# IC_Adapter_2x20_Panel.net
KiCad netlist of a schematic drawn in EAGLE
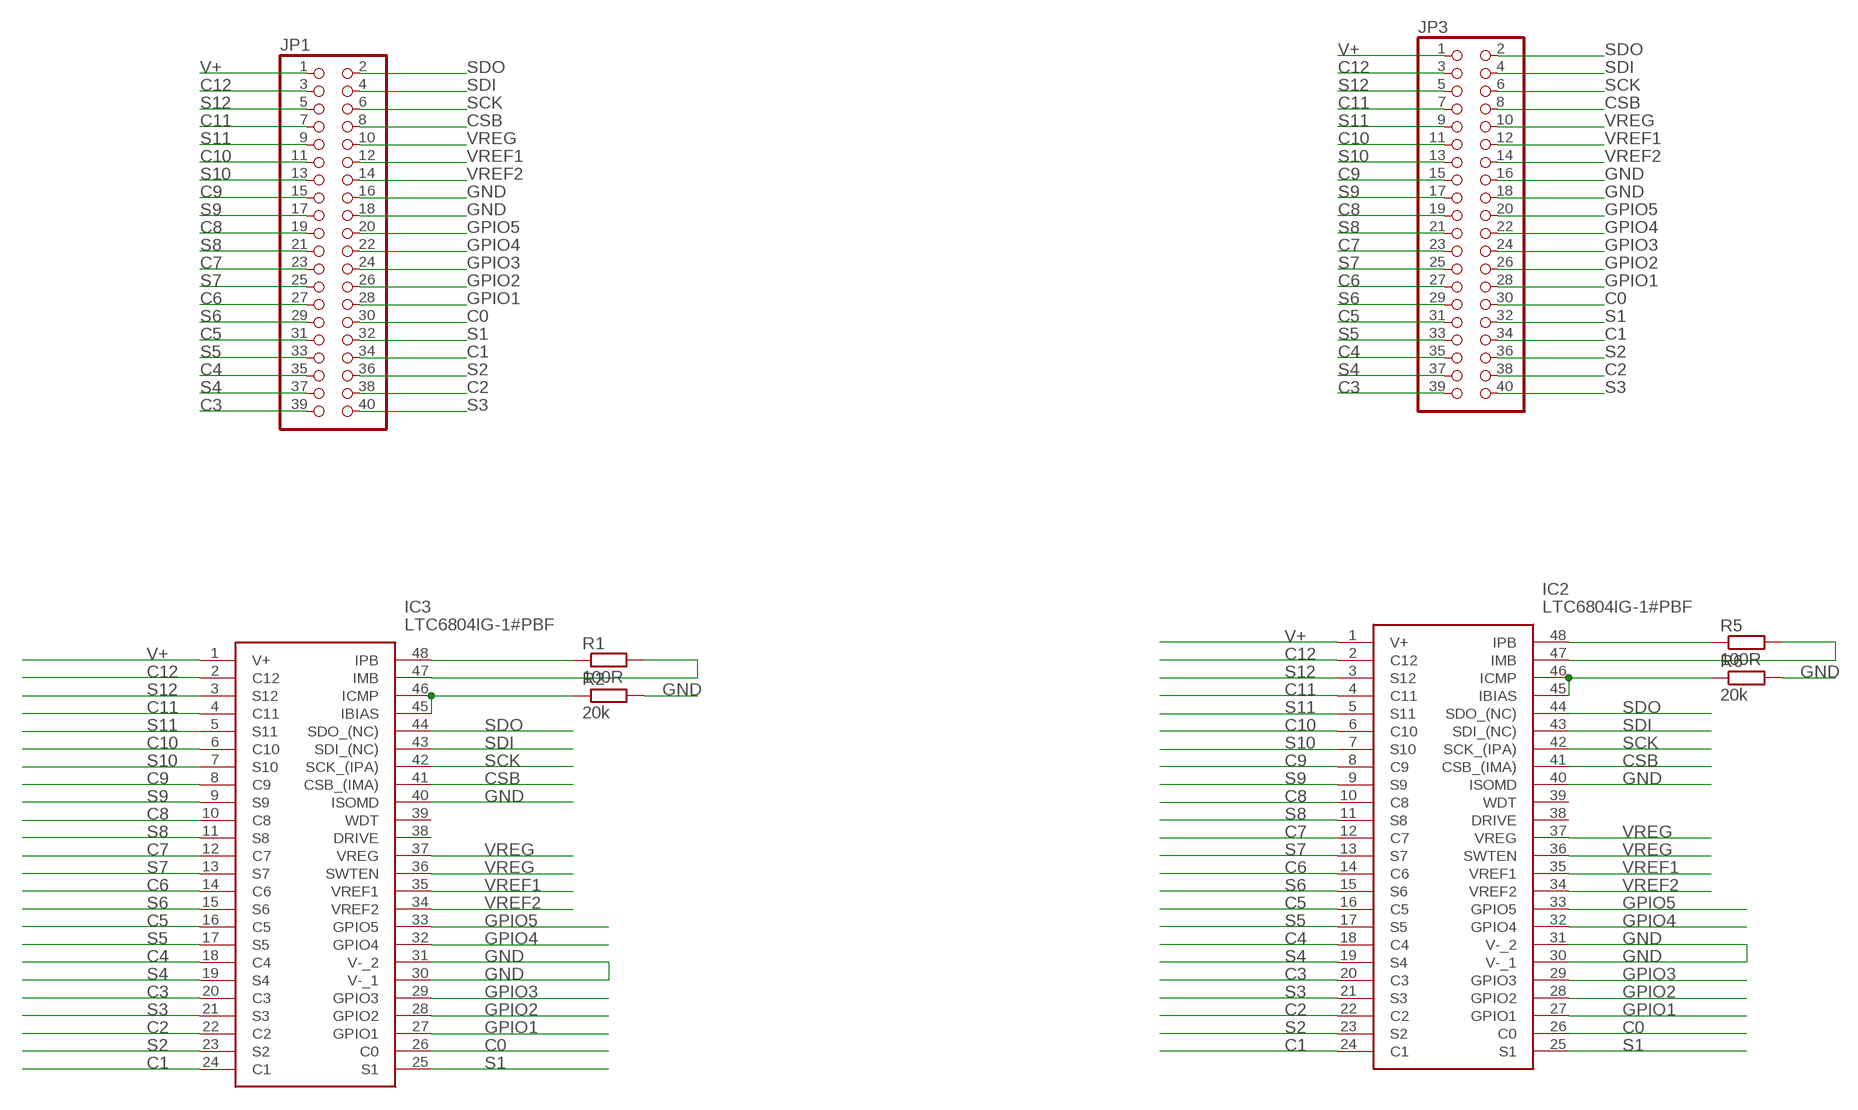
[diagram p0: schematic, sheet 1, part 1 of 2]
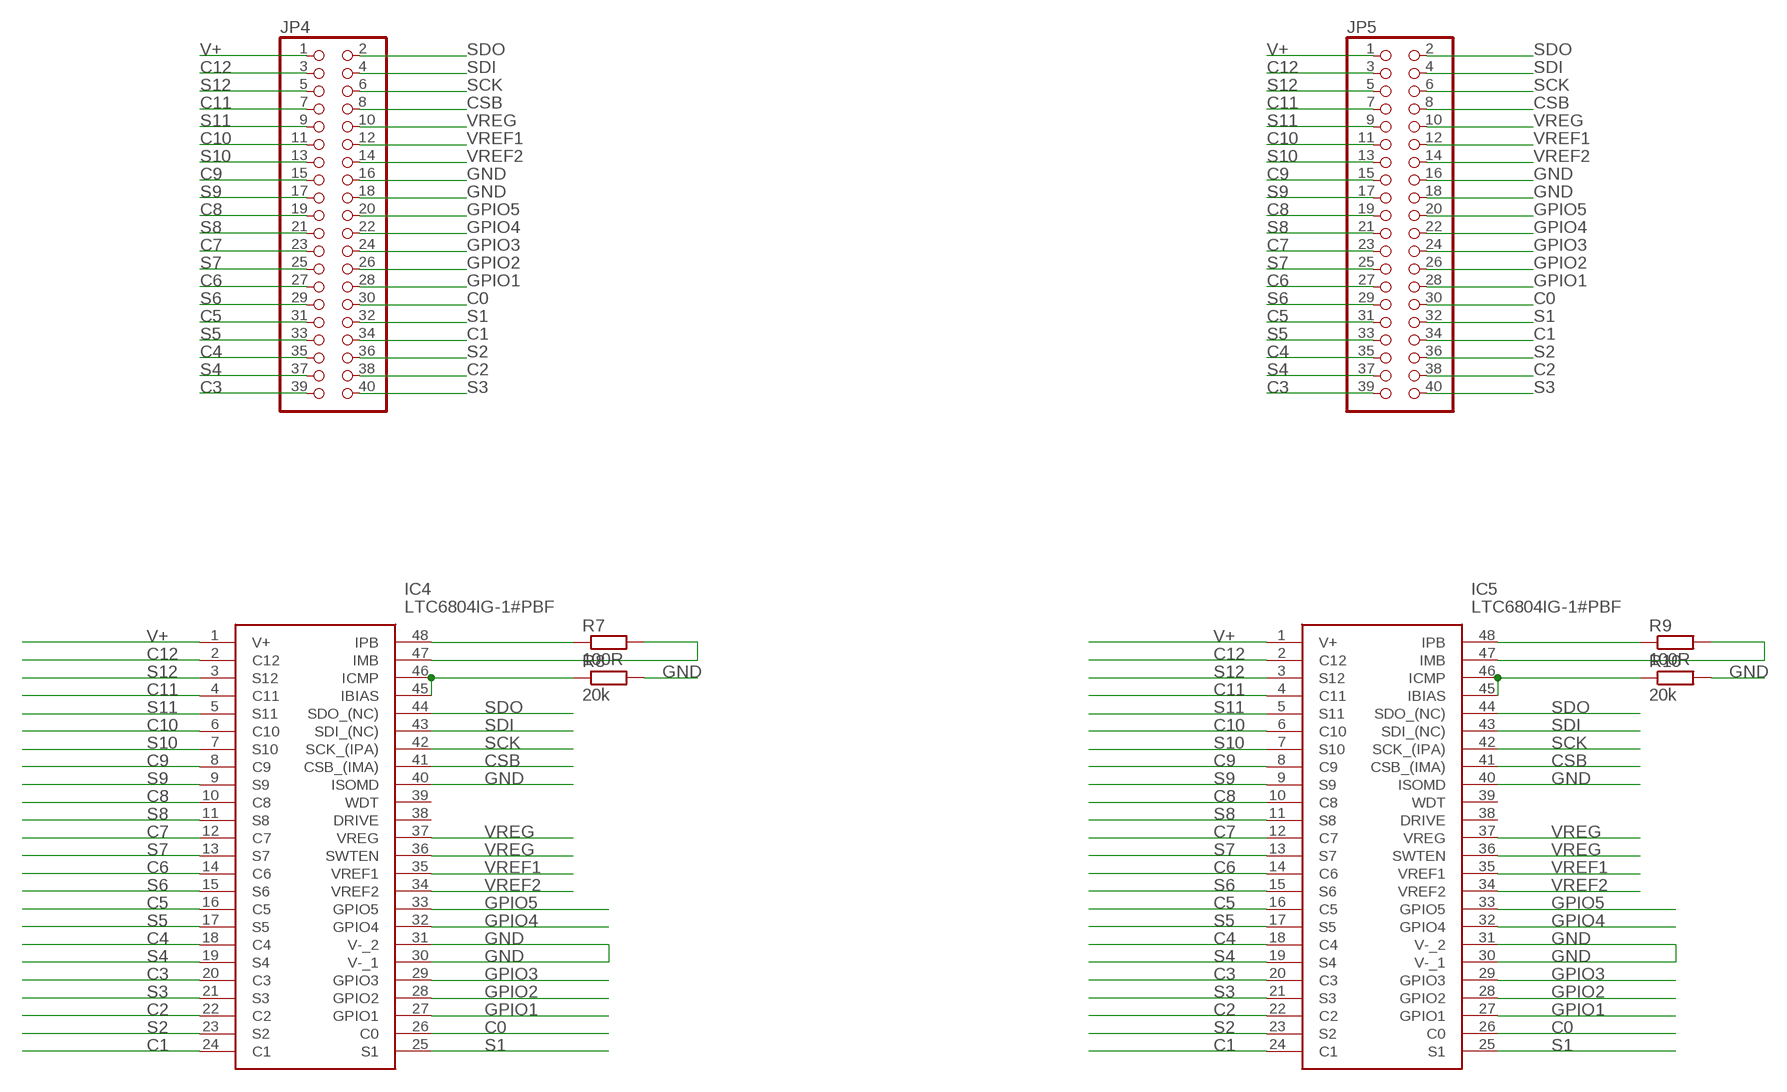
[diagram p1: schematic, sheet 1, part 2 of 2]

(export (version "E")
  (design (tool "Eeschema 10.0.6"))
  (components
    (comp (ref "IC2")
      (value "LTC6804IG-1#PBF")
      (footprint "eagle-import:SOP50P780X200-48N")
      (fields (field (name "MOUSER_PART_NUMBER") "584-LTC6804IG-1#PBF"))
      (libsource (lib "eagle-import") (part "LTC6804IG-1#PBF"))
    )
    (comp (ref "IC3")
      (value "LTC6804IG-1#PBF")
      (footprint "eagle-import:SOP50P780X200-48N")
      (fields (field (name "MOUSER_PART_NUMBER") "584-LTC6804IG-1#PBF"))
      (libsource (lib "eagle-import") (part "LTC6804IG-1#PBF"))
    )
    (comp (ref "IC4")
      (value "LTC6804IG-1#PBF")
      (footprint "eagle-import:SOP50P780X200-48N")
      (fields (field (name "MOUSER_PART_NUMBER") "584-LTC6804IG-1#PBF"))
      (libsource (lib "eagle-import") (part "LTC6804IG-1#PBF"))
    )
    (comp (ref "IC5")
      (value "LTC6804IG-1#PBF")
      (footprint "eagle-import:SOP50P780X200-48N")
      (fields (field (name "MOUSER_PART_NUMBER") "584-LTC6804IG-1#PBF"))
      (libsource (lib "eagle-import") (part "LTC6804IG-1#PBF"))
    )
    (comp (ref "JP1")
      (value "PINHD-2X20")
      (footprint "eagle-import:2X20")
      (libsource (lib "eagle-import") (part "PINHD-2X20"))
    )
    (comp (ref "JP3")
      (value "PINHD-2X20")
      (footprint "eagle-import:2X20")
      (libsource (lib "eagle-import") (part "PINHD-2X20"))
    )
    (comp (ref "JP4")
      (value "PINHD-2X20")
      (footprint "eagle-import:2X20")
      (libsource (lib "eagle-import") (part "PINHD-2X20"))
    )
    (comp (ref "JP5")
      (value "PINHD-2X20")
      (footprint "eagle-import:2X20")
      (libsource (lib "eagle-import") (part "PINHD-2X20"))
    )
    (comp (ref "R1")
      (value "100R")
      (footprint "eagle-import:R0805")
      (libsource (lib "eagle-import") (part "R-EU_R0805"))
    )
    (comp (ref "R2")
      (value "20k")
      (footprint "eagle-import:R0805")
      (libsource (lib "eagle-import") (part "R-EU_R0805"))
    )
    (comp (ref "R5")
      (value "100R")
      (footprint "eagle-import:R0805")
      (libsource (lib "eagle-import") (part "R-EU_R0805"))
    )
    (comp (ref "R6")
      (value "20k")
      (footprint "eagle-import:R0805")
      (libsource (lib "eagle-import") (part "R-EU_R0805"))
    )
    (comp (ref "R7")
      (value "100R")
      (footprint "eagle-import:R0805")
      (libsource (lib "eagle-import") (part "R-EU_R0805"))
    )
    (comp (ref "R8")
      (value "20k")
      (footprint "eagle-import:R0805")
      (libsource (lib "eagle-import") (part "R-EU_R0805"))
    )
    (comp (ref "R9")
      (value "100R")
      (footprint "eagle-import:R0805")
      (libsource (lib "eagle-import") (part "R-EU_R0805"))
    )
    (comp (ref "R10")
      (value "20k")
      (footprint "eagle-import:R0805")
      (libsource (lib "eagle-import") (part "R-EU_R0805"))
    )
  )
  (nets
    (net (code "1") (name "/C0") (class "Default")
      (node (ref "IC2") (pin "26") (pinfunction "C0_26") (pintype "bidirectional"))
      (node (ref "IC3") (pin "26") (pinfunction "C0_26") (pintype "bidirectional"))
      (node (ref "IC4") (pin "26") (pinfunction "C0_26") (pintype "bidirectional"))
      (node (ref "IC5") (pin "26") (pinfunction "C0_26") (pintype "bidirectional"))
      (node (ref "JP1") (pin "30") (pinfunction "30_30") (pintype "passive"))
      (node (ref "JP3") (pin "30") (pinfunction "30_30") (pintype "passive"))
      (node (ref "JP4") (pin "30") (pinfunction "30_30") (pintype "passive"))
      (node (ref "JP5") (pin "30") (pinfunction "30_30") (pintype "passive"))
    )
    (net (code "2") (name "/C1") (class "Default")
      (node (ref "IC2") (pin "24") (pinfunction "C1_24") (pintype "bidirectional"))
      (node (ref "IC3") (pin "24") (pinfunction "C1_24") (pintype "bidirectional"))
      (node (ref "IC4") (pin "24") (pinfunction "C1_24") (pintype "bidirectional"))
      (node (ref "IC5") (pin "24") (pinfunction "C1_24") (pintype "bidirectional"))
      (node (ref "JP1") (pin "34") (pinfunction "34_34") (pintype "passive"))
      (node (ref "JP3") (pin "34") (pinfunction "34_34") (pintype "passive"))
      (node (ref "JP4") (pin "34") (pinfunction "34_34") (pintype "passive"))
      (node (ref "JP5") (pin "34") (pinfunction "34_34") (pintype "passive"))
    )
    (net (code "3") (name "/C2") (class "Default")
      (node (ref "IC2") (pin "22") (pinfunction "C2_22") (pintype "bidirectional"))
      (node (ref "IC3") (pin "22") (pinfunction "C2_22") (pintype "bidirectional"))
      (node (ref "IC4") (pin "22") (pinfunction "C2_22") (pintype "bidirectional"))
      (node (ref "IC5") (pin "22") (pinfunction "C2_22") (pintype "bidirectional"))
      (node (ref "JP1") (pin "38") (pinfunction "38_38") (pintype "passive"))
      (node (ref "JP3") (pin "38") (pinfunction "38_38") (pintype "passive"))
      (node (ref "JP4") (pin "38") (pinfunction "38_38") (pintype "passive"))
      (node (ref "JP5") (pin "38") (pinfunction "38_38") (pintype "passive"))
    )
    (net (code "4") (name "/C3") (class "Default")
      (node (ref "IC2") (pin "20") (pinfunction "C3_20") (pintype "bidirectional"))
      (node (ref "IC3") (pin "20") (pinfunction "C3_20") (pintype "bidirectional"))
      (node (ref "IC4") (pin "20") (pinfunction "C3_20") (pintype "bidirectional"))
      (node (ref "IC5") (pin "20") (pinfunction "C3_20") (pintype "bidirectional"))
      (node (ref "JP1") (pin "39") (pinfunction "39_39") (pintype "passive"))
      (node (ref "JP3") (pin "39") (pinfunction "39_39") (pintype "passive"))
      (node (ref "JP4") (pin "39") (pinfunction "39_39") (pintype "passive"))
      (node (ref "JP5") (pin "39") (pinfunction "39_39") (pintype "passive"))
    )
    (net (code "5") (name "/C4") (class "Default")
      (node (ref "IC2") (pin "18") (pinfunction "C4_18") (pintype "bidirectional"))
      (node (ref "IC3") (pin "18") (pinfunction "C4_18") (pintype "bidirectional"))
      (node (ref "IC4") (pin "18") (pinfunction "C4_18") (pintype "bidirectional"))
      (node (ref "IC5") (pin "18") (pinfunction "C4_18") (pintype "bidirectional"))
      (node (ref "JP1") (pin "35") (pinfunction "35_35") (pintype "passive"))
      (node (ref "JP3") (pin "35") (pinfunction "35_35") (pintype "passive"))
      (node (ref "JP4") (pin "35") (pinfunction "35_35") (pintype "passive"))
      (node (ref "JP5") (pin "35") (pinfunction "35_35") (pintype "passive"))
    )
    (net (code "6") (name "/C5") (class "Default")
      (node (ref "IC2") (pin "16") (pinfunction "C5_16") (pintype "bidirectional"))
      (node (ref "IC3") (pin "16") (pinfunction "C5_16") (pintype "bidirectional"))
      (node (ref "IC4") (pin "16") (pinfunction "C5_16") (pintype "bidirectional"))
      (node (ref "IC5") (pin "16") (pinfunction "C5_16") (pintype "bidirectional"))
      (node (ref "JP1") (pin "31") (pinfunction "31_31") (pintype "passive"))
      (node (ref "JP3") (pin "31") (pinfunction "31_31") (pintype "passive"))
      (node (ref "JP4") (pin "31") (pinfunction "31_31") (pintype "passive"))
      (node (ref "JP5") (pin "31") (pinfunction "31_31") (pintype "passive"))
    )
    (net (code "7") (name "/C6") (class "Default")
      (node (ref "IC2") (pin "14") (pinfunction "C6_14") (pintype "bidirectional"))
      (node (ref "IC3") (pin "14") (pinfunction "C6_14") (pintype "bidirectional"))
      (node (ref "IC4") (pin "14") (pinfunction "C6_14") (pintype "bidirectional"))
      (node (ref "IC5") (pin "14") (pinfunction "C6_14") (pintype "bidirectional"))
      (node (ref "JP1") (pin "27") (pinfunction "27_27") (pintype "passive"))
      (node (ref "JP3") (pin "27") (pinfunction "27_27") (pintype "passive"))
      (node (ref "JP4") (pin "27") (pinfunction "27_27") (pintype "passive"))
      (node (ref "JP5") (pin "27") (pinfunction "27_27") (pintype "passive"))
    )
    (net (code "8") (name "/C7") (class "Default")
      (node (ref "IC2") (pin "12") (pinfunction "C7_12") (pintype "bidirectional"))
      (node (ref "IC3") (pin "12") (pinfunction "C7_12") (pintype "bidirectional"))
      (node (ref "IC4") (pin "12") (pinfunction "C7_12") (pintype "bidirectional"))
      (node (ref "IC5") (pin "12") (pinfunction "C7_12") (pintype "bidirectional"))
      (node (ref "JP1") (pin "23") (pinfunction "23_23") (pintype "passive"))
      (node (ref "JP3") (pin "23") (pinfunction "23_23") (pintype "passive"))
      (node (ref "JP4") (pin "23") (pinfunction "23_23") (pintype "passive"))
      (node (ref "JP5") (pin "23") (pinfunction "23_23") (pintype "passive"))
    )
    (net (code "9") (name "/C8") (class "Default")
      (node (ref "IC2") (pin "10") (pinfunction "C8_10") (pintype "bidirectional"))
      (node (ref "IC3") (pin "10") (pinfunction "C8_10") (pintype "bidirectional"))
      (node (ref "IC4") (pin "10") (pinfunction "C8_10") (pintype "bidirectional"))
      (node (ref "IC5") (pin "10") (pinfunction "C8_10") (pintype "bidirectional"))
      (node (ref "JP1") (pin "19") (pinfunction "19_19") (pintype "passive"))
      (node (ref "JP3") (pin "19") (pinfunction "19_19") (pintype "passive"))
      (node (ref "JP4") (pin "19") (pinfunction "19_19") (pintype "passive"))
      (node (ref "JP5") (pin "19") (pinfunction "19_19") (pintype "passive"))
    )
    (net (code "10") (name "/C9") (class "Default")
      (node (ref "IC2") (pin "8") (pinfunction "C9_8") (pintype "bidirectional"))
      (node (ref "IC3") (pin "8") (pinfunction "C9_8") (pintype "bidirectional"))
      (node (ref "IC4") (pin "8") (pinfunction "C9_8") (pintype "bidirectional"))
      (node (ref "IC5") (pin "8") (pinfunction "C9_8") (pintype "bidirectional"))
      (node (ref "JP1") (pin "15") (pinfunction "15_15") (pintype "passive"))
      (node (ref "JP3") (pin "15") (pinfunction "15_15") (pintype "passive"))
      (node (ref "JP4") (pin "15") (pinfunction "15_15") (pintype "passive"))
      (node (ref "JP5") (pin "15") (pinfunction "15_15") (pintype "passive"))
    )
    (net (code "11") (name "/C10") (class "Default")
      (node (ref "IC2") (pin "6") (pinfunction "C10_6") (pintype "bidirectional"))
      (node (ref "IC3") (pin "6") (pinfunction "C10_6") (pintype "bidirectional"))
      (node (ref "IC4") (pin "6") (pinfunction "C10_6") (pintype "bidirectional"))
      (node (ref "IC5") (pin "6") (pinfunction "C10_6") (pintype "bidirectional"))
      (node (ref "JP1") (pin "11") (pinfunction "11_11") (pintype "passive"))
      (node (ref "JP3") (pin "11") (pinfunction "11_11") (pintype "passive"))
      (node (ref "JP4") (pin "11") (pinfunction "11_11") (pintype "passive"))
      (node (ref "JP5") (pin "11") (pinfunction "11_11") (pintype "passive"))
    )
    (net (code "12") (name "/C11") (class "Default")
      (node (ref "IC2") (pin "4") (pinfunction "C11_4") (pintype "bidirectional"))
      (node (ref "IC3") (pin "4") (pinfunction "C11_4") (pintype "bidirectional"))
      (node (ref "IC4") (pin "4") (pinfunction "C11_4") (pintype "bidirectional"))
      (node (ref "IC5") (pin "4") (pinfunction "C11_4") (pintype "bidirectional"))
      (node (ref "JP1") (pin "7") (pinfunction "7_7") (pintype "passive"))
      (node (ref "JP3") (pin "7") (pinfunction "7_7") (pintype "passive"))
      (node (ref "JP4") (pin "7") (pinfunction "7_7") (pintype "passive"))
      (node (ref "JP5") (pin "7") (pinfunction "7_7") (pintype "passive"))
    )
    (net (code "13") (name "/C12") (class "Default")
      (node (ref "IC2") (pin "2") (pinfunction "C12_2") (pintype "bidirectional"))
      (node (ref "IC3") (pin "2") (pinfunction "C12_2") (pintype "bidirectional"))
      (node (ref "IC4") (pin "2") (pinfunction "C12_2") (pintype "bidirectional"))
      (node (ref "IC5") (pin "2") (pinfunction "C12_2") (pintype "bidirectional"))
      (node (ref "JP1") (pin "3") (pinfunction "3_3") (pintype "passive"))
      (node (ref "JP3") (pin "3") (pinfunction "3_3") (pintype "passive"))
      (node (ref "JP4") (pin "3") (pinfunction "3_3") (pintype "passive"))
      (node (ref "JP5") (pin "3") (pinfunction "3_3") (pintype "passive"))
    )
    (net (code "14") (name "/CSB") (class "Default")
      (node (ref "IC2") (pin "41") (pinfunction "CSB_(IMA)_41") (pintype "bidirectional"))
      (node (ref "IC3") (pin "41") (pinfunction "CSB_(IMA)_41") (pintype "bidirectional"))
      (node (ref "IC4") (pin "41") (pinfunction "CSB_(IMA)_41") (pintype "bidirectional"))
      (node (ref "IC5") (pin "41") (pinfunction "CSB_(IMA)_41") (pintype "bidirectional"))
      (node (ref "JP1") (pin "8") (pinfunction "8_8") (pintype "passive"))
      (node (ref "JP3") (pin "8") (pinfunction "8_8") (pintype "passive"))
      (node (ref "JP4") (pin "8") (pinfunction "8_8") (pintype "passive"))
      (node (ref "JP5") (pin "8") (pinfunction "8_8") (pintype "passive"))
    )
    (net (code "15") (name "/GND") (class "Default")
      (node (ref "IC2") (pin "30") (pinfunction "V-_1_30") (pintype "bidirectional"))
      (node (ref "IC2") (pin "31") (pinfunction "V-_2_31") (pintype "bidirectional"))
      (node (ref "IC2") (pin "40") (pinfunction "ISOMD_40") (pintype "bidirectional"))
      (node (ref "IC3") (pin "30") (pinfunction "V-_1_30") (pintype "bidirectional"))
      (node (ref "IC3") (pin "31") (pinfunction "V-_2_31") (pintype "bidirectional"))
      (node (ref "IC3") (pin "40") (pinfunction "ISOMD_40") (pintype "bidirectional"))
      (node (ref "IC4") (pin "30") (pinfunction "V-_1_30") (pintype "bidirectional"))
      (node (ref "IC4") (pin "31") (pinfunction "V-_2_31") (pintype "bidirectional"))
      (node (ref "IC4") (pin "40") (pinfunction "ISOMD_40") (pintype "bidirectional"))
      (node (ref "IC5") (pin "30") (pinfunction "V-_1_30") (pintype "bidirectional"))
      (node (ref "IC5") (pin "31") (pinfunction "V-_2_31") (pintype "bidirectional"))
      (node (ref "IC5") (pin "40") (pinfunction "ISOMD_40") (pintype "bidirectional"))
      (node (ref "JP1") (pin "16") (pinfunction "16_16") (pintype "passive"))
      (node (ref "JP1") (pin "18") (pinfunction "18_18") (pintype "passive"))
      (node (ref "JP3") (pin "16") (pinfunction "16_16") (pintype "passive"))
      (node (ref "JP3") (pin "18") (pinfunction "18_18") (pintype "passive"))
      (node (ref "JP4") (pin "16") (pinfunction "16_16") (pintype "passive"))
      (node (ref "JP4") (pin "18") (pinfunction "18_18") (pintype "passive"))
      (node (ref "JP5") (pin "16") (pinfunction "16_16") (pintype "passive"))
      (node (ref "JP5") (pin "18") (pinfunction "18_18") (pintype "passive"))
      (node (ref "R10") (pin "2") (pinfunction "2_2") (pintype "passive"))
      (node (ref "R2") (pin "2") (pinfunction "2_2") (pintype "passive"))
      (node (ref "R6") (pin "2") (pinfunction "2_2") (pintype "passive"))
      (node (ref "R8") (pin "2") (pinfunction "2_2") (pintype "passive"))
    )
    (net (code "16") (name "/GPIO1") (class "Default")
      (node (ref "IC2") (pin "27") (pinfunction "GPIO1_27") (pintype "bidirectional"))
      (node (ref "IC3") (pin "27") (pinfunction "GPIO1_27") (pintype "bidirectional"))
      (node (ref "IC4") (pin "27") (pinfunction "GPIO1_27") (pintype "bidirectional"))
      (node (ref "IC5") (pin "27") (pinfunction "GPIO1_27") (pintype "bidirectional"))
      (node (ref "JP1") (pin "28") (pinfunction "28_28") (pintype "passive"))
      (node (ref "JP3") (pin "28") (pinfunction "28_28") (pintype "passive"))
      (node (ref "JP4") (pin "28") (pinfunction "28_28") (pintype "passive"))
      (node (ref "JP5") (pin "28") (pinfunction "28_28") (pintype "passive"))
    )
    (net (code "17") (name "/GPIO2") (class "Default")
      (node (ref "IC2") (pin "28") (pinfunction "GPIO2_28") (pintype "bidirectional"))
      (node (ref "IC3") (pin "28") (pinfunction "GPIO2_28") (pintype "bidirectional"))
      (node (ref "IC4") (pin "28") (pinfunction "GPIO2_28") (pintype "bidirectional"))
      (node (ref "IC5") (pin "28") (pinfunction "GPIO2_28") (pintype "bidirectional"))
      (node (ref "JP1") (pin "26") (pinfunction "26_26") (pintype "passive"))
      (node (ref "JP3") (pin "26") (pinfunction "26_26") (pintype "passive"))
      (node (ref "JP4") (pin "26") (pinfunction "26_26") (pintype "passive"))
      (node (ref "JP5") (pin "26") (pinfunction "26_26") (pintype "passive"))
    )
    (net (code "18") (name "/GPIO3") (class "Default")
      (node (ref "IC2") (pin "29") (pinfunction "GPIO3_29") (pintype "bidirectional"))
      (node (ref "IC3") (pin "29") (pinfunction "GPIO3_29") (pintype "bidirectional"))
      (node (ref "IC4") (pin "29") (pinfunction "GPIO3_29") (pintype "bidirectional"))
      (node (ref "IC5") (pin "29") (pinfunction "GPIO3_29") (pintype "bidirectional"))
      (node (ref "JP1") (pin "24") (pinfunction "24_24") (pintype "passive"))
      (node (ref "JP3") (pin "24") (pinfunction "24_24") (pintype "passive"))
      (node (ref "JP4") (pin "24") (pinfunction "24_24") (pintype "passive"))
      (node (ref "JP5") (pin "24") (pinfunction "24_24") (pintype "passive"))
    )
    (net (code "19") (name "/GPIO4") (class "Default")
      (node (ref "IC2") (pin "32") (pinfunction "GPIO4_32") (pintype "bidirectional"))
      (node (ref "IC3") (pin "32") (pinfunction "GPIO4_32") (pintype "bidirectional"))
      (node (ref "IC4") (pin "32") (pinfunction "GPIO4_32") (pintype "bidirectional"))
      (node (ref "IC5") (pin "32") (pinfunction "GPIO4_32") (pintype "bidirectional"))
      (node (ref "JP1") (pin "22") (pinfunction "22_22") (pintype "passive"))
      (node (ref "JP3") (pin "22") (pinfunction "22_22") (pintype "passive"))
      (node (ref "JP4") (pin "22") (pinfunction "22_22") (pintype "passive"))
      (node (ref "JP5") (pin "22") (pinfunction "22_22") (pintype "passive"))
    )
    (net (code "20") (name "/GPIO5") (class "Default")
      (node (ref "IC2") (pin "33") (pinfunction "GPIO5_33") (pintype "bidirectional"))
      (node (ref "IC3") (pin "33") (pinfunction "GPIO5_33") (pintype "bidirectional"))
      (node (ref "IC4") (pin "33") (pinfunction "GPIO5_33") (pintype "bidirectional"))
      (node (ref "IC5") (pin "33") (pinfunction "GPIO5_33") (pintype "bidirectional"))
      (node (ref "JP1") (pin "20") (pinfunction "20_20") (pintype "passive"))
      (node (ref "JP3") (pin "20") (pinfunction "20_20") (pintype "passive"))
      (node (ref "JP4") (pin "20") (pinfunction "20_20") (pintype "passive"))
      (node (ref "JP5") (pin "20") (pinfunction "20_20") (pintype "passive"))
    )
    (net (code "21") (name "/S1") (class "Default")
      (node (ref "IC2") (pin "25") (pinfunction "S1_25") (pintype "bidirectional"))
      (node (ref "IC3") (pin "25") (pinfunction "S1_25") (pintype "bidirectional"))
      (node (ref "IC4") (pin "25") (pinfunction "S1_25") (pintype "bidirectional"))
      (node (ref "IC5") (pin "25") (pinfunction "S1_25") (pintype "bidirectional"))
      (node (ref "JP1") (pin "32") (pinfunction "32_32") (pintype "passive"))
      (node (ref "JP3") (pin "32") (pinfunction "32_32") (pintype "passive"))
      (node (ref "JP4") (pin "32") (pinfunction "32_32") (pintype "passive"))
      (node (ref "JP5") (pin "32") (pinfunction "32_32") (pintype "passive"))
    )
    (net (code "22") (name "/S2") (class "Default")
      (node (ref "IC2") (pin "23") (pinfunction "S2_23") (pintype "bidirectional"))
      (node (ref "IC3") (pin "23") (pinfunction "S2_23") (pintype "bidirectional"))
      (node (ref "IC4") (pin "23") (pinfunction "S2_23") (pintype "bidirectional"))
      (node (ref "IC5") (pin "23") (pinfunction "S2_23") (pintype "bidirectional"))
      (node (ref "JP1") (pin "36") (pinfunction "36_36") (pintype "passive"))
      (node (ref "JP3") (pin "36") (pinfunction "36_36") (pintype "passive"))
      (node (ref "JP4") (pin "36") (pinfunction "36_36") (pintype "passive"))
      (node (ref "JP5") (pin "36") (pinfunction "36_36") (pintype "passive"))
    )
    (net (code "23") (name "/S3") (class "Default")
      (node (ref "IC2") (pin "21") (pinfunction "S3_21") (pintype "bidirectional"))
      (node (ref "IC3") (pin "21") (pinfunction "S3_21") (pintype "bidirectional"))
      (node (ref "IC4") (pin "21") (pinfunction "S3_21") (pintype "bidirectional"))
      (node (ref "IC5") (pin "21") (pinfunction "S3_21") (pintype "bidirectional"))
      (node (ref "JP1") (pin "40") (pinfunction "40_40") (pintype "passive"))
      (node (ref "JP3") (pin "40") (pinfunction "40_40") (pintype "passive"))
      (node (ref "JP4") (pin "40") (pinfunction "40_40") (pintype "passive"))
      (node (ref "JP5") (pin "40") (pinfunction "40_40") (pintype "passive"))
    )
    (net (code "24") (name "/S4") (class "Default")
      (node (ref "IC2") (pin "19") (pinfunction "S4_19") (pintype "bidirectional"))
      (node (ref "IC3") (pin "19") (pinfunction "S4_19") (pintype "bidirectional"))
      (node (ref "IC4") (pin "19") (pinfunction "S4_19") (pintype "bidirectional"))
      (node (ref "IC5") (pin "19") (pinfunction "S4_19") (pintype "bidirectional"))
      (node (ref "JP1") (pin "37") (pinfunction "37_37") (pintype "passive"))
      (node (ref "JP3") (pin "37") (pinfunction "37_37") (pintype "passive"))
      (node (ref "JP4") (pin "37") (pinfunction "37_37") (pintype "passive"))
      (node (ref "JP5") (pin "37") (pinfunction "37_37") (pintype "passive"))
    )
    (net (code "25") (name "/S5") (class "Default")
      (node (ref "IC2") (pin "17") (pinfunction "S5_17") (pintype "bidirectional"))
      (node (ref "IC3") (pin "17") (pinfunction "S5_17") (pintype "bidirectional"))
      (node (ref "IC4") (pin "17") (pinfunction "S5_17") (pintype "bidirectional"))
      (node (ref "IC5") (pin "17") (pinfunction "S5_17") (pintype "bidirectional"))
      (node (ref "JP1") (pin "33") (pinfunction "33_33") (pintype "passive"))
      (node (ref "JP3") (pin "33") (pinfunction "33_33") (pintype "passive"))
      (node (ref "JP4") (pin "33") (pinfunction "33_33") (pintype "passive"))
      (node (ref "JP5") (pin "33") (pinfunction "33_33") (pintype "passive"))
    )
    (net (code "26") (name "/S6") (class "Default")
      (node (ref "IC2") (pin "15") (pinfunction "S6_15") (pintype "bidirectional"))
      (node (ref "IC3") (pin "15") (pinfunction "S6_15") (pintype "bidirectional"))
      (node (ref "IC4") (pin "15") (pinfunction "S6_15") (pintype "bidirectional"))
      (node (ref "IC5") (pin "15") (pinfunction "S6_15") (pintype "bidirectional"))
      (node (ref "JP1") (pin "29") (pinfunction "29_29") (pintype "passive"))
      (node (ref "JP3") (pin "29") (pinfunction "29_29") (pintype "passive"))
      (node (ref "JP4") (pin "29") (pinfunction "29_29") (pintype "passive"))
      (node (ref "JP5") (pin "29") (pinfunction "29_29") (pintype "passive"))
    )
    (net (code "27") (name "/S7") (class "Default")
      (node (ref "IC2") (pin "13") (pinfunction "S7_13") (pintype "bidirectional"))
      (node (ref "IC3") (pin "13") (pinfunction "S7_13") (pintype "bidirectional"))
      (node (ref "IC4") (pin "13") (pinfunction "S7_13") (pintype "bidirectional"))
      (node (ref "IC5") (pin "13") (pinfunction "S7_13") (pintype "bidirectional"))
      (node (ref "JP1") (pin "25") (pinfunction "25_25") (pintype "passive"))
      (node (ref "JP3") (pin "25") (pinfunction "25_25") (pintype "passive"))
      (node (ref "JP4") (pin "25") (pinfunction "25_25") (pintype "passive"))
      (node (ref "JP5") (pin "25") (pinfunction "25_25") (pintype "passive"))
    )
    (net (code "28") (name "/S8") (class "Default")
      (node (ref "IC2") (pin "11") (pinfunction "S8_11") (pintype "bidirectional"))
      (node (ref "IC3") (pin "11") (pinfunction "S8_11") (pintype "bidirectional"))
      (node (ref "IC4") (pin "11") (pinfunction "S8_11") (pintype "bidirectional"))
      (node (ref "IC5") (pin "11") (pinfunction "S8_11") (pintype "bidirectional"))
      (node (ref "JP1") (pin "21") (pinfunction "21_21") (pintype "passive"))
      (node (ref "JP3") (pin "21") (pinfunction "21_21") (pintype "passive"))
      (node (ref "JP4") (pin "21") (pinfunction "21_21") (pintype "passive"))
      (node (ref "JP5") (pin "21") (pinfunction "21_21") (pintype "passive"))
    )
    (net (code "29") (name "/S9") (class "Default")
      (node (ref "IC2") (pin "9") (pinfunction "S9_9") (pintype "bidirectional"))
      (node (ref "IC3") (pin "9") (pinfunction "S9_9") (pintype "bidirectional"))
      (node (ref "IC4") (pin "9") (pinfunction "S9_9") (pintype "bidirectional"))
      (node (ref "IC5") (pin "9") (pinfunction "S9_9") (pintype "bidirectional"))
      (node (ref "JP1") (pin "17") (pinfunction "17_17") (pintype "passive"))
      (node (ref "JP3") (pin "17") (pinfunction "17_17") (pintype "passive"))
      (node (ref "JP4") (pin "17") (pinfunction "17_17") (pintype "passive"))
      (node (ref "JP5") (pin "17") (pinfunction "17_17") (pintype "passive"))
    )
    (net (code "30") (name "/S10") (class "Default")
      (node (ref "IC2") (pin "7") (pinfunction "S10_7") (pintype "bidirectional"))
      (node (ref "IC3") (pin "7") (pinfunction "S10_7") (pintype "bidirectional"))
      (node (ref "IC4") (pin "7") (pinfunction "S10_7") (pintype "bidirectional"))
      (node (ref "IC5") (pin "7") (pinfunction "S10_7") (pintype "bidirectional"))
      (node (ref "JP1") (pin "13") (pinfunction "13_13") (pintype "passive"))
      (node (ref "JP3") (pin "13") (pinfunction "13_13") (pintype "passive"))
      (node (ref "JP4") (pin "13") (pinfunction "13_13") (pintype "passive"))
      (node (ref "JP5") (pin "13") (pinfunction "13_13") (pintype "passive"))
    )
    (net (code "31") (name "/S11") (class "Default")
      (node (ref "IC2") (pin "5") (pinfunction "S11_5") (pintype "bidirectional"))
      (node (ref "IC3") (pin "5") (pinfunction "S11_5") (pintype "bidirectional"))
      (node (ref "IC4") (pin "5") (pinfunction "S11_5") (pintype "bidirectional"))
      (node (ref "IC5") (pin "5") (pinfunction "S11_5") (pintype "bidirectional"))
      (node (ref "JP1") (pin "9") (pinfunction "9_9") (pintype "passive"))
      (node (ref "JP3") (pin "9") (pinfunction "9_9") (pintype "passive"))
      (node (ref "JP4") (pin "9") (pinfunction "9_9") (pintype "passive"))
      (node (ref "JP5") (pin "9") (pinfunction "9_9") (pintype "passive"))
    )
    (net (code "32") (name "/S12") (class "Default")
      (node (ref "IC2") (pin "3") (pinfunction "S12_3") (pintype "bidirectional"))
      (node (ref "IC3") (pin "3") (pinfunction "S12_3") (pintype "bidirectional"))
      (node (ref "IC4") (pin "3") (pinfunction "S12_3") (pintype "bidirectional"))
      (node (ref "IC5") (pin "3") (pinfunction "S12_3") (pintype "bidirectional"))
      (node (ref "JP1") (pin "5") (pinfunction "5_5") (pintype "passive"))
      (node (ref "JP3") (pin "5") (pinfunction "5_5") (pintype "passive"))
      (node (ref "JP4") (pin "5") (pinfunction "5_5") (pintype "passive"))
      (node (ref "JP5") (pin "5") (pinfunction "5_5") (pintype "passive"))
    )
    (net (code "33") (name "/SCK") (class "Default")
      (node (ref "IC2") (pin "42") (pinfunction "SCK_(IPA)_42") (pintype "bidirectional"))
      (node (ref "IC3") (pin "42") (pinfunction "SCK_(IPA)_42") (pintype "bidirectional"))
      (node (ref "IC4") (pin "42") (pinfunction "SCK_(IPA)_42") (pintype "bidirectional"))
      (node (ref "IC5") (pin "42") (pinfunction "SCK_(IPA)_42") (pintype "bidirectional"))
      (node (ref "JP1") (pin "6") (pinfunction "6_6") (pintype "passive"))
      (node (ref "JP3") (pin "6") (pinfunction "6_6") (pintype "passive"))
      (node (ref "JP4") (pin "6") (pinfunction "6_6") (pintype "passive"))
      (node (ref "JP5") (pin "6") (pinfunction "6_6") (pintype "passive"))
    )
    (net (code "34") (name "/SDI") (class "Default")
      (node (ref "IC2") (pin "43") (pinfunction "SDI_(NC)_43") (pintype "bidirectional"))
      (node (ref "IC3") (pin "43") (pinfunction "SDI_(NC)_43") (pintype "bidirectional"))
      (node (ref "IC4") (pin "43") (pinfunction "SDI_(NC)_43") (pintype "bidirectional"))
      (node (ref "IC5") (pin "43") (pinfunction "SDI_(NC)_43") (pintype "bidirectional"))
      (node (ref "JP1") (pin "4") (pinfunction "4_4") (pintype "passive"))
      (node (ref "JP3") (pin "4") (pinfunction "4_4") (pintype "passive"))
      (node (ref "JP4") (pin "4") (pinfunction "4_4") (pintype "passive"))
      (node (ref "JP5") (pin "4") (pinfunction "4_4") (pintype "passive"))
    )
    (net (code "35") (name "/SDO") (class "Default")
      (node (ref "IC2") (pin "44") (pinfunction "SDO_(NC)_44") (pintype "bidirectional"))
      (node (ref "IC3") (pin "44") (pinfunction "SDO_(NC)_44") (pintype "bidirectional"))
      (node (ref "IC4") (pin "44") (pinfunction "SDO_(NC)_44") (pintype "bidirectional"))
      (node (ref "IC5") (pin "44") (pinfunction "SDO_(NC)_44") (pintype "bidirectional"))
      (node (ref "JP1") (pin "2") (pinfunction "2_2") (pintype "passive"))
      (node (ref "JP3") (pin "2") (pinfunction "2_2") (pintype "passive"))
      (node (ref "JP4") (pin "2") (pinfunction "2_2") (pintype "passive"))
      (node (ref "JP5") (pin "2") (pinfunction "2_2") (pintype "passive"))
    )
    (net (code "36") (name "/V+") (class "Default")
      (node (ref "IC2") (pin "1") (pinfunction "V+_1") (pintype "bidirectional"))
      (node (ref "IC3") (pin "1") (pinfunction "V+_1") (pintype "bidirectional"))
      (node (ref "IC4") (pin "1") (pinfunction "V+_1") (pintype "bidirectional"))
      (node (ref "IC5") (pin "1") (pinfunction "V+_1") (pintype "bidirectional"))
      (node (ref "JP1") (pin "1") (pinfunction "1_1") (pintype "passive"))
      (node (ref "JP3") (pin "1") (pinfunction "1_1") (pintype "passive"))
      (node (ref "JP4") (pin "1") (pinfunction "1_1") (pintype "passive"))
      (node (ref "JP5") (pin "1") (pinfunction "1_1") (pintype "passive"))
    )
    (net (code "37") (name "/VREF1") (class "Default")
      (node (ref "IC2") (pin "35") (pinfunction "VREF1_35") (pintype "bidirectional"))
      (node (ref "IC3") (pin "35") (pinfunction "VREF1_35") (pintype "bidirectional"))
      (node (ref "IC4") (pin "35") (pinfunction "VREF1_35") (pintype "bidirectional"))
      (node (ref "IC5") (pin "35") (pinfunction "VREF1_35") (pintype "bidirectional"))
      (node (ref "JP1") (pin "12") (pinfunction "12_12") (pintype "passive"))
      (node (ref "JP3") (pin "12") (pinfunction "12_12") (pintype "passive"))
      (node (ref "JP4") (pin "12") (pinfunction "12_12") (pintype "passive"))
      (node (ref "JP5") (pin "12") (pinfunction "12_12") (pintype "passive"))
    )
    (net (code "38") (name "/VREF2") (class "Default")
      (node (ref "IC2") (pin "34") (pinfunction "VREF2_34") (pintype "bidirectional"))
      (node (ref "IC3") (pin "34") (pinfunction "VREF2_34") (pintype "bidirectional"))
      (node (ref "IC4") (pin "34") (pinfunction "VREF2_34") (pintype "bidirectional"))
      (node (ref "IC5") (pin "34") (pinfunction "VREF2_34") (pintype "bidirectional"))
      (node (ref "JP1") (pin "14") (pinfunction "14_14") (pintype "passive"))
      (node (ref "JP3") (pin "14") (pinfunction "14_14") (pintype "passive"))
      (node (ref "JP4") (pin "14") (pinfunction "14_14") (pintype "passive"))
      (node (ref "JP5") (pin "14") (pinfunction "14_14") (pintype "passive"))
    )
    (net (code "39") (name "/VREG") (class "Default")
      (node (ref "IC2") (pin "36") (pinfunction "SWTEN_36") (pintype "bidirectional"))
      (node (ref "IC2") (pin "37") (pinfunction "VREG_37") (pintype "bidirectional"))
      (node (ref "IC3") (pin "36") (pinfunction "SWTEN_36") (pintype "bidirectional"))
      (node (ref "IC3") (pin "37") (pinfunction "VREG_37") (pintype "bidirectional"))
      (node (ref "IC4") (pin "36") (pinfunction "SWTEN_36") (pintype "bidirectional"))
      (node (ref "IC4") (pin "37") (pinfunction "VREG_37") (pintype "bidirectional"))
      (node (ref "IC5") (pin "36") (pinfunction "SWTEN_36") (pintype "bidirectional"))
      (node (ref "IC5") (pin "37") (pinfunction "VREG_37") (pintype "bidirectional"))
      (node (ref "JP1") (pin "10") (pinfunction "10_10") (pintype "passive"))
      (node (ref "JP3") (pin "10") (pinfunction "10_10") (pintype "passive"))
      (node (ref "JP4") (pin "10") (pinfunction "10_10") (pintype "passive"))
      (node (ref "JP5") (pin "10") (pinfunction "10_10") (pintype "passive"))
    )
    (net (code "40") (name "Net-(IC2-IBIAS)") (class "Default")
      (node (ref "IC2") (pin "45") (pinfunction "IBIAS_45") (pintype "bidirectional"))
      (node (ref "IC2") (pin "46") (pinfunction "ICMP_46") (pintype "bidirectional"))
      (node (ref "R6") (pin "1") (pinfunction "1_1") (pintype "passive"))
    )
    (net (code "41") (name "Net-(IC2-IMB)") (class "Default")
      (node (ref "IC2") (pin "47") (pinfunction "IMB_47") (pintype "bidirectional"))
      (node (ref "R5") (pin "2") (pinfunction "2_2") (pintype "passive"))
    )
    (net (code "42") (name "Net-(IC2-IPB)") (class "Default")
      (node (ref "IC2") (pin "48") (pinfunction "IPB_48") (pintype "bidirectional"))
      (node (ref "R5") (pin "1") (pinfunction "1_1") (pintype "passive"))
    )
    (net (code "43") (name "Net-(IC3-IBIAS)") (class "Default")
      (node (ref "IC3") (pin "45") (pinfunction "IBIAS_45") (pintype "bidirectional"))
      (node (ref "IC3") (pin "46") (pinfunction "ICMP_46") (pintype "bidirectional"))
      (node (ref "R2") (pin "1") (pinfunction "1_1") (pintype "passive"))
    )
    (net (code "44") (name "Net-(IC3-IMB)") (class "Default")
      (node (ref "IC3") (pin "47") (pinfunction "IMB_47") (pintype "bidirectional"))
      (node (ref "R1") (pin "2") (pinfunction "2_2") (pintype "passive"))
    )
    (net (code "45") (name "Net-(IC3-IPB)") (class "Default")
      (node (ref "IC3") (pin "48") (pinfunction "IPB_48") (pintype "bidirectional"))
      (node (ref "R1") (pin "1") (pinfunction "1_1") (pintype "passive"))
    )
    (net (code "46") (name "Net-(IC4-IBIAS)") (class "Default")
      (node (ref "IC4") (pin "45") (pinfunction "IBIAS_45") (pintype "bidirectional"))
      (node (ref "IC4") (pin "46") (pinfunction "ICMP_46") (pintype "bidirectional"))
      (node (ref "R8") (pin "1") (pinfunction "1_1") (pintype "passive"))
    )
    (net (code "47") (name "Net-(IC4-IMB)") (class "Default")
      (node (ref "IC4") (pin "47") (pinfunction "IMB_47") (pintype "bidirectional"))
      (node (ref "R7") (pin "2") (pinfunction "2_2") (pintype "passive"))
    )
    (net (code "48") (name "Net-(IC4-IPB)") (class "Default")
      (node (ref "IC4") (pin "48") (pinfunction "IPB_48") (pintype "bidirectional"))
      (node (ref "R7") (pin "1") (pinfunction "1_1") (pintype "passive"))
    )
    (net (code "49") (name "Net-(IC5-IBIAS)") (class "Default")
      (node (ref "IC5") (pin "45") (pinfunction "IBIAS_45") (pintype "bidirectional"))
      (node (ref "IC5") (pin "46") (pinfunction "ICMP_46") (pintype "bidirectional"))
      (node (ref "R10") (pin "1") (pinfunction "1_1") (pintype "passive"))
    )
    (net (code "50") (name "Net-(IC5-IMB)") (class "Default")
      (node (ref "IC5") (pin "47") (pinfunction "IMB_47") (pintype "bidirectional"))
      (node (ref "R9") (pin "2") (pinfunction "2_2") (pintype "passive"))
    )
    (net (code "51") (name "Net-(IC5-IPB)") (class "Default")
      (node (ref "IC5") (pin "48") (pinfunction "IPB_48") (pintype "bidirectional"))
      (node (ref "R9") (pin "1") (pinfunction "1_1") (pintype "passive"))
    )
    (net (code "52") (name "unconnected-(IC2-DRIVE-Pad38)") (class "Default")
      (node (ref "IC2") (pin "38") (pinfunction "DRIVE_38") (pintype "bidirectional"))
    )
    (net (code "53") (name "unconnected-(IC2-WDT-Pad39)") (class "Default")
      (node (ref "IC2") (pin "39") (pinfunction "WDT_39") (pintype "bidirectional"))
    )
    (net (code "54") (name "unconnected-(IC3-DRIVE-Pad38)") (class "Default")
      (node (ref "IC3") (pin "38") (pinfunction "DRIVE_38") (pintype "bidirectional"))
    )
    (net (code "55") (name "unconnected-(IC3-WDT-Pad39)") (class "Default")
      (node (ref "IC3") (pin "39") (pinfunction "WDT_39") (pintype "bidirectional"))
    )
    (net (code "56") (name "unconnected-(IC4-DRIVE-Pad38)") (class "Default")
      (node (ref "IC4") (pin "38") (pinfunction "DRIVE_38") (pintype "bidirectional"))
    )
    (net (code "57") (name "unconnected-(IC4-WDT-Pad39)") (class "Default")
      (node (ref "IC4") (pin "39") (pinfunction "WDT_39") (pintype "bidirectional"))
    )
    (net (code "58") (name "unconnected-(IC5-DRIVE-Pad38)") (class "Default")
      (node (ref "IC5") (pin "38") (pinfunction "DRIVE_38") (pintype "bidirectional"))
    )
    (net (code "59") (name "unconnected-(IC5-WDT-Pad39)") (class "Default")
      (node (ref "IC5") (pin "39") (pinfunction "WDT_39") (pintype "bidirectional"))
    )
  )
)
